# GPS_radiologger_v18_LoRa_only.net
KiCad netlist of a schematic drawn in EAGLE
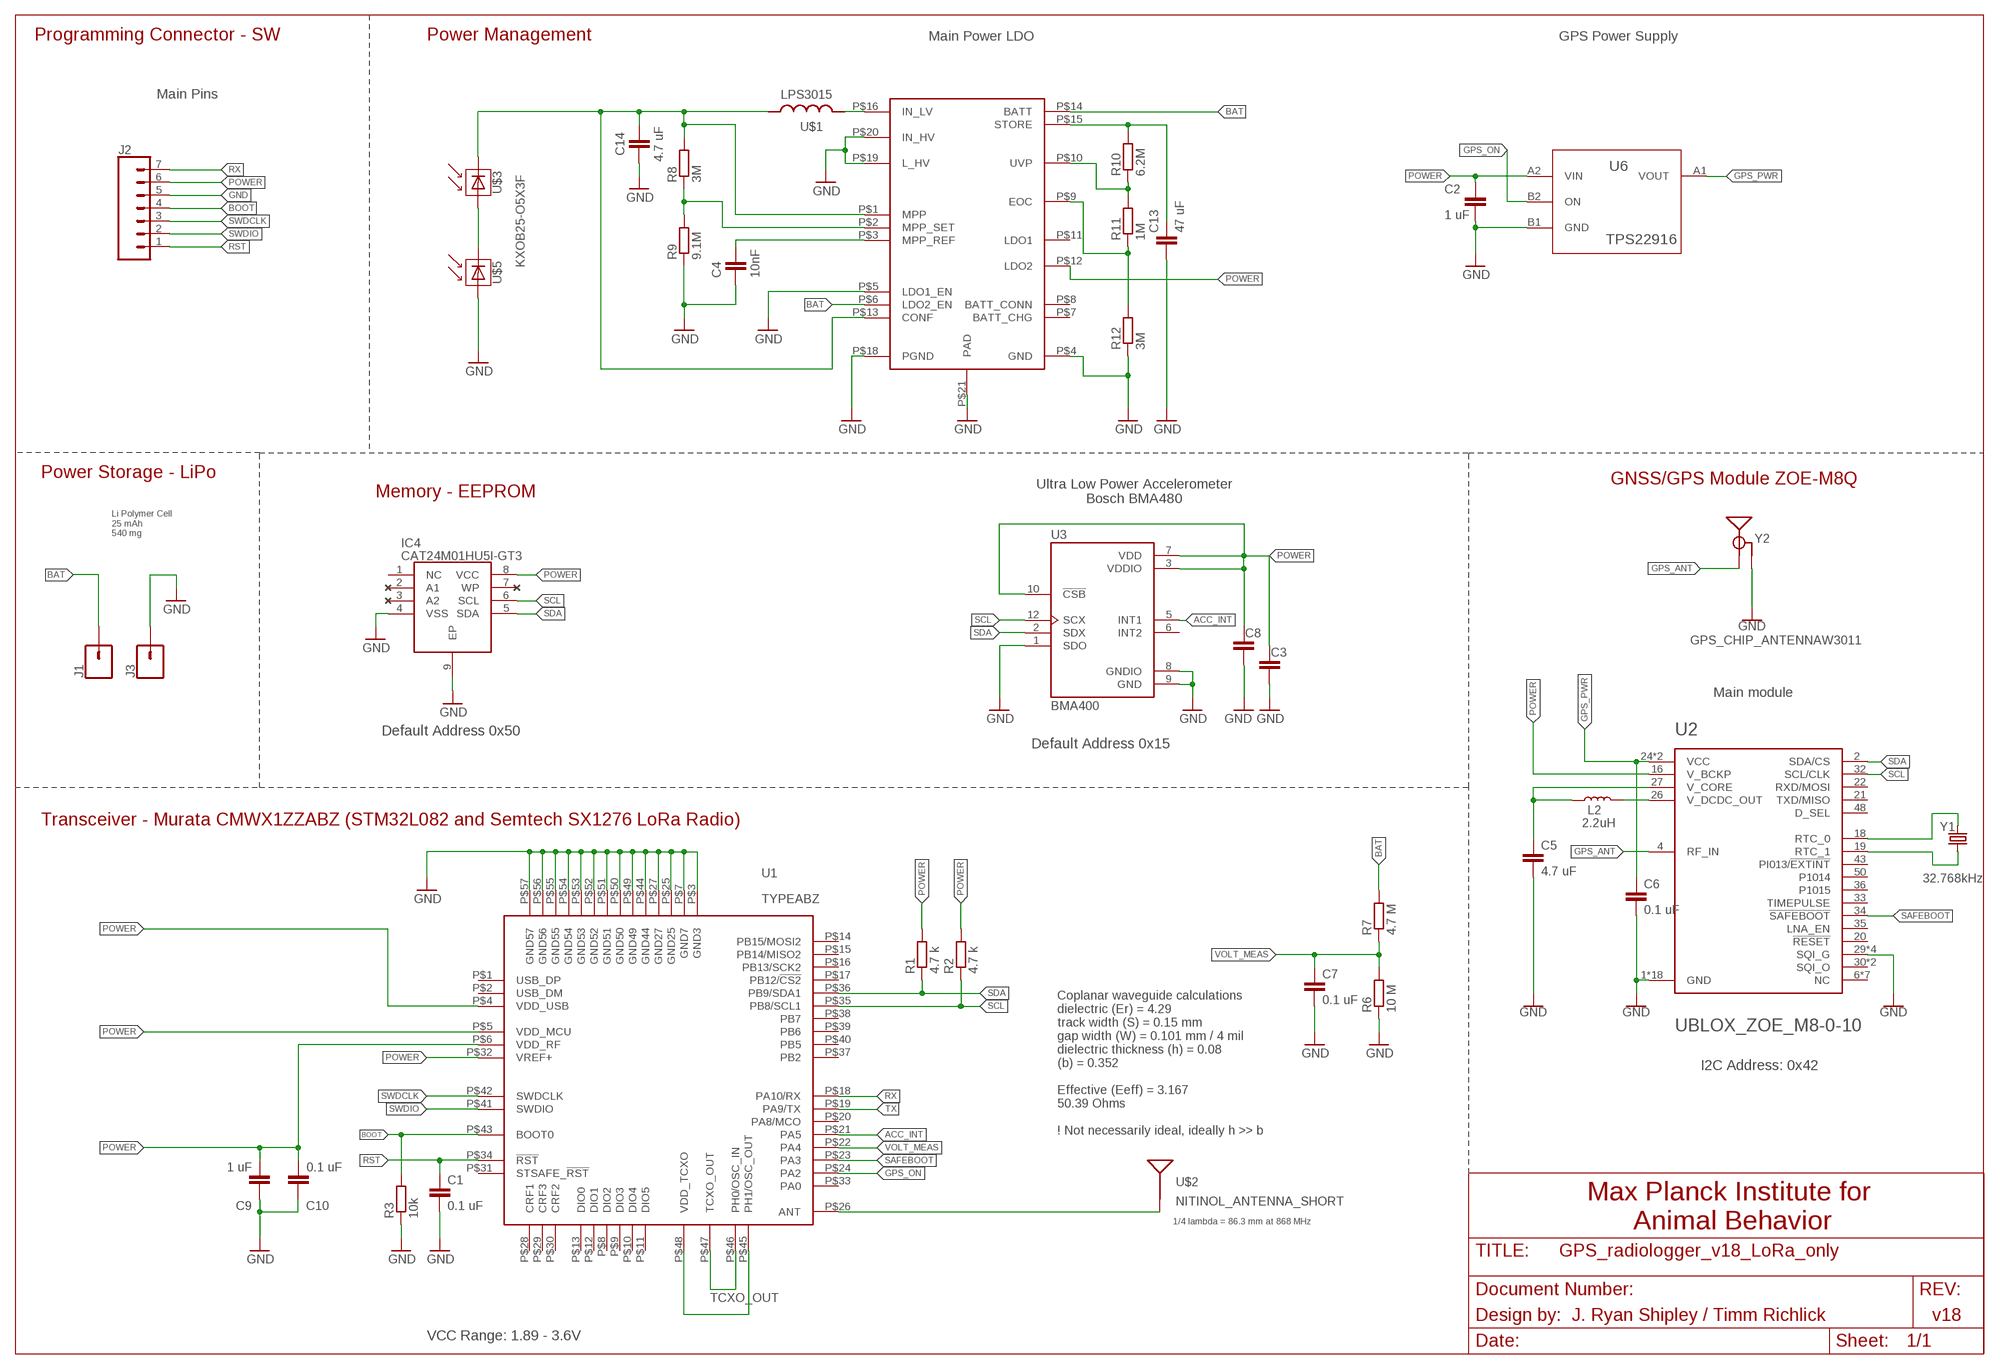
[diagram p0: schematic, sheet 1]

(export (version "E")
  (design (tool "Eeschema 10.0.6"))
  (components
    (comp (ref "C1")
      (value "0.1 uF")
      (footprint "eagle-import:C0201")
      (libsource (lib "eagle-import") (part "C-EUC0201"))
    )
    (comp (ref "C2")
      (value "1 uF")
      (footprint "eagle-import:C0201")
      (libsource (lib "eagle-import") (part "C-EUC0201"))
    )
    (comp (ref "C3")
      (value "C-EUC0201")
      (footprint "eagle-import:C0201")
      (libsource (lib "eagle-import") (part "C-EUC0201"))
    )
    (comp (ref "C4")
      (value "10nF")
      (footprint "eagle-import:C0201")
      (libsource (lib "eagle-import") (part "C-EUC0201"))
    )
    (comp (ref "C5")
      (value "4.7 uF")
      (footprint "eagle-import:C0201")
      (libsource (lib "eagle-import") (part "C-EUC0201"))
    )
    (comp (ref "C6")
      (value "0.1 uF")
      (footprint "eagle-import:C0201")
      (libsource (lib "eagle-import") (part "C-EUC0201"))
    )
    (comp (ref "C7")
      (value "0.1 uF")
      (footprint "eagle-import:C0201")
      (libsource (lib "eagle-import") (part "C-EUC0201"))
    )
    (comp (ref "C8")
      (value "C-EUC0201")
      (footprint "eagle-import:C0201")
      (libsource (lib "eagle-import") (part "C-EUC0201"))
    )
    (comp (ref "C9")
      (value "1 uF")
      (footprint "eagle-import:C0201")
      (libsource (lib "eagle-import") (part "C-EUC0201"))
    )
    (comp (ref "C10")
      (value "0.1 uF")
      (footprint "eagle-import:C0201")
      (libsource (lib "eagle-import") (part "C-EUC0201"))
    )
    (comp (ref "C13")
      (value "47 uF")
      (footprint "eagle-import:C0805K")
      (libsource (lib "eagle-import") (part "C-EUC0805K"))
    )
    (comp (ref "C14")
      (value "4.7 uF")
      (footprint "eagle-import:C0201")
      (libsource (lib "eagle-import") (part "C-EUC0201"))
    )
    (comp (ref "IC4")
      (value "CAT24M01HU5I-GT3")
      (footprint "eagle-import:SON50P300X200X55-9N")
      (fields
        (field (name "MOUSER_PART_NUMBER") "863-CAT24M01HU5I-GT3")
        (field (name "RS_PART_NUMBER") "7814831P")
      )
      (libsource (lib "eagle-import") (part "CAT24M01HU5I-GT3"))
    )
    (comp (ref "J1")
      (value "CONN_01PTH_NO_SILK_YES_STOP")
      (footprint "eagle-import:1X01_NO_SILK")
      (libsource (lib "eagle-import") (part "CONN_01PTH_NO_SILK_YES_STOP"))
    )
    (comp (ref "J2")
      (value "CONN_07NO_SILK")
      (footprint "eagle-import:1X07_NO_SILK")
      (libsource (lib "eagle-import") (part "CONN_07NO_SILK"))
    )
    (comp (ref "J3")
      (value "CONN_01PTH_NO_SILK_YES_STOP")
      (footprint "eagle-import:1X01_NO_SILK")
      (libsource (lib "eagle-import") (part "CONN_01PTH_NO_SILK_YES_STOP"))
    )
    (comp (ref "L2")
      (value "2.2uH")
      (footprint "eagle-import:0806")
      (libsource (lib "eagle-import") (part "2.2μH_SHIELDED_INDUCTOR"))
    )
    (comp (ref "R1")
      (value "4.7 k")
      (footprint "eagle-import:R0201")
      (libsource (lib "eagle-import") (part "R-EU_R0201"))
    )
    (comp (ref "R2")
      (value "4.7 k")
      (footprint "eagle-import:R0201")
      (libsource (lib "eagle-import") (part "R-EU_R0201"))
    )
    (comp (ref "R3")
      (value "10k")
      (footprint "eagle-import:R0201")
      (libsource (lib "eagle-import") (part "R-EU_R0201"))
    )
    (comp (ref "R6")
      (value "10 M")
      (footprint "eagle-import:R0201")
      (libsource (lib "eagle-import") (part "R-EU_R0201"))
    )
    (comp (ref "R7")
      (value "4.7 M")
      (footprint "eagle-import:R0201")
      (libsource (lib "eagle-import") (part "R-EU_R0201"))
    )
    (comp (ref "R8")
      (value "3M")
      (footprint "eagle-import:R0201")
      (libsource (lib "eagle-import") (part "R-EU_R0201"))
    )
    (comp (ref "R9")
      (value "9.1M")
      (footprint "eagle-import:R0201")
      (libsource (lib "eagle-import") (part "R-EU_R0201"))
    )
    (comp (ref "R10")
      (value "6.2M")
      (footprint "eagle-import:R0201")
      (libsource (lib "eagle-import") (part "R-EU_R0201"))
    )
    (comp (ref "R11")
      (value "1M")
      (footprint "eagle-import:R0201")
      (libsource (lib "eagle-import") (part "R-EU_R0201"))
    )
    (comp (ref "R12")
      (value "3M")
      (footprint "eagle-import:R0201")
      (libsource (lib "eagle-import") (part "R-EU_R0201"))
    )
    (comp (ref "U$1")
      (value "LPS3015")
      (footprint "eagle-import:LPS_3015")
      (libsource (lib "eagle-import") (part "LPS3015"))
    )
    (comp (ref "U$2")
      (value "NITINOL_ANTENNA_SHORT")
      (footprint "eagle-import:ICARUS_NITINOL_ANTENNA_SHORT")
      (libsource (lib "eagle-import") (part "NITINOL_ANTENNA_SHORT"))
    )
    (comp (ref "U$3")
      (value "KXOB25-O5X3F")
      (footprint "eagle-import:KXOB25-05X3F")
      (libsource (lib "eagle-import") (part "KXOB25-O5X3F"))
    )
    (comp (ref "U$5")
      (value "KXOB25-O5X3F")
      (footprint "eagle-import:KXOB25-05X3F")
      (libsource (lib "eagle-import") (part "KXOB25-O5X3F"))
    )
    (comp (ref "U1")
      (value "TYPEABZ")
      (footprint "eagle-import:TYPEABZ")
      (libsource (lib "eagle-import") (part "TYPEABZ"))
    )
    (comp (ref "U2")
      (value "UBLOX_ZOE_M8-0-10")
      (footprint "eagle-import:UBLOX_ZOE_M8-0-10")
      (libsource (lib "eagle-import") (part "UBLOX_ZOE_M8-0-10"))
    )
    (comp (ref "U3")
      (value "BMA400")
      (footprint "eagle-import:XDCR_BMA400")
      (fields (field (name "MF") "Bosch Sensortec"))
      (libsource (lib "eagle-import") (part "BMA400"))
    )
    (comp (ref "U4")
      (value "SPV1050")
      (footprint "eagle-import:SPV1050")
      (libsource (lib "eagle-import") (part "SPV1050"))
    )
    (comp (ref "U6")
      (value "TPS22916")
      (footprint "eagle-import:TPS22916")
      (fields (field (name "MF") "Texas Instruments") (field (name "MP") "LP5900TL-3.0"))
      (libsource (lib "eagle-import") (part "TPS22916"))
    )
    (comp (ref "Y1")
      (value "32.768kHz")
      (footprint "eagle-import:CRYSTAL-SMD-3.2X1.5MM")
      (libsource (lib "eagle-import") (part "CRYSTAL-32.768KHZSMD-3.2X1.5"))
    )
    (comp (ref "Y2")
      (value "GPS_CHIP_ANTENNAW3011")
      (footprint "eagle-import:W3011")
      (libsource (lib "eagle-import") (part "GPS_CHIP_ANTENNAW3011"))
    )
  )
  (nets
    (net (code "1") (name "/TCXO_OUT") (class "Default")
      (node (ref "U1") (pin "P$46") (pinfunction "PH0/OSC_IN_P$46") (pintype "bidirectional"))
      (node (ref "U1") (pin "P$47") (pinfunction "TCXO_OUT_P$47") (pintype "bidirectional"))
    )
    (net (code "2") (name "ACC_INT") (class "Default")
      (node (ref "U1") (pin "P$21") (pinfunction "PA5_P$21") (pintype "bidirectional"))
      (node (ref "U3") (pin "5") (pinfunction "INT1_5") (pintype "bidirectional"))
    )
    (net (code "3") (name "BAT") (class "Default")
      (node (ref "J1") (pin "1") (pinfunction "1_1") (pintype "passive"))
      (node (ref "R7") (pin "2") (pinfunction "2_2") (pintype "passive"))
      (node (ref "U4") (pin "P$14") (pinfunction "BATT_P$14") (pintype "bidirectional"))
      (node (ref "U4") (pin "P$6") (pinfunction "LDO2_EN_P$6") (pintype "input"))
    )
    (net (code "4") (name "BOOT") (class "Default")
      (node (ref "J2") (pin "4") (pinfunction "4_4") (pintype "passive"))
      (node (ref "R3") (pin "2") (pinfunction "2_2") (pintype "passive"))
      (node (ref "U1") (pin "P$43") (pinfunction "BOOT0_P$43") (pintype "bidirectional"))
    )
    (net (code "5") (name "GND") (class "Default")
      (node (ref "C1") (pin "2") (pinfunction "2_2") (pintype "passive"))
      (node (ref "C10") (pin "1") (pinfunction "1_1") (pintype "passive"))
      (node (ref "C13") (pin "2") (pinfunction "2_2") (pintype "passive"))
      (node (ref "C14") (pin "2") (pinfunction "2_2") (pintype "passive"))
      (node (ref "C2") (pin "2") (pinfunction "2_2") (pintype "passive"))
      (node (ref "C3") (pin "2") (pinfunction "2_2") (pintype "passive"))
      (node (ref "C4") (pin "2") (pinfunction "2_2") (pintype "passive"))
      (node (ref "C5") (pin "2") (pinfunction "2_2") (pintype "passive"))
      (node (ref "C6") (pin "2") (pinfunction "2_2") (pintype "passive"))
      (node (ref "C7") (pin "2") (pinfunction "2_2") (pintype "passive"))
      (node (ref "C8") (pin "2") (pinfunction "2_2") (pintype "passive"))
      (node (ref "C9") (pin "1") (pinfunction "1_1") (pintype "passive"))
      (node (ref "IC4") (pin "4") (pinfunction "VSS_4") (pintype "power_in"))
      (node (ref "IC4") (pin "9") (pinfunction "EP_9") (pintype "bidirectional"))
      (node (ref "J2") (pin "5") (pinfunction "5_5") (pintype "passive"))
      (node (ref "J3") (pin "1") (pinfunction "1_1") (pintype "passive"))
      (node (ref "R12") (pin "1") (pinfunction "1_1") (pintype "passive"))
      (node (ref "R3") (pin "1") (pinfunction "1_1") (pintype "passive"))
      (node (ref "R6") (pin "1") (pinfunction "1_1") (pintype "passive"))
      (node (ref "R9") (pin "1") (pinfunction "1_1") (pintype "passive"))
      (node (ref "U$5") (pin "P$2") (pinfunction "MINUS_P$2") (pintype "passive"))
      (node (ref "U1") (pin "P$25") (pinfunction "GND25_P$25") (pintype "power_in"))
      (node (ref "U1") (pin "P$27") (pinfunction "GND27_P$27") (pintype "power_in"))
      (node (ref "U1") (pin "P$3") (pinfunction "GND3_P$3") (pintype "power_in"))
      (node (ref "U1") (pin "P$44") (pinfunction "GND44_P$44") (pintype "power_in"))
      (node (ref "U1") (pin "P$49") (pinfunction "GND49_P$49") (pintype "power_in"))
      (node (ref "U1") (pin "P$50") (pinfunction "GND50_P$50") (pintype "power_in"))
      (node (ref "U1") (pin "P$51") (pinfunction "GND51_P$51") (pintype "power_in"))
      (node (ref "U1") (pin "P$52") (pinfunction "GND52_P$52") (pintype "power_in"))
      (node (ref "U1") (pin "P$53") (pinfunction "GND53_P$53") (pintype "power_in"))
      (node (ref "U1") (pin "P$54") (pinfunction "GND54_P$54") (pintype "power_in"))
      (node (ref "U1") (pin "P$55") (pinfunction "GND55_P$55") (pintype "power_in"))
      (node (ref "U1") (pin "P$56") (pinfunction "GND56_P$56") (pintype "power_in"))
      (node (ref "U1") (pin "P$57") (pinfunction "GND57_P$57") (pintype "power_in"))
      (node (ref "U1") (pin "P$7") (pinfunction "GND7_P$7") (pintype "power_in"))
      (node (ref "U2") (pin "1") (pinfunction "GND_1") (pintype "power_in"))
      (node (ref "U2") (pin "10") (pinfunction "GND_10") (pintype "power_in"))
      (node (ref "U2") (pin "11") (pinfunction "GND_11") (pintype "power_in"))
      (node (ref "U2") (pin "12") (pinfunction "GND_12") (pintype "power_in"))
      (node (ref "U2") (pin "17") (pinfunction "GND_17") (pintype "power_in"))
      (node (ref "U2") (pin "23") (pinfunction "GND_23") (pintype "power_in"))
      (node (ref "U2") (pin "29") (pinfunction "SQI_G_29") (pintype "bidirectional"))
      (node (ref "U2") (pin "3") (pinfunction "GND_3") (pintype "power_in"))
      (node (ref "U2") (pin "31") (pinfunction "SQI_G_31") (pintype "bidirectional"))
      (node (ref "U2") (pin "37") (pinfunction "GND_37") (pintype "power_in"))
      (node (ref "U2") (pin "38") (pinfunction "GND_38") (pintype "power_in"))
      (node (ref "U2") (pin "39") (pinfunction "GND_39") (pintype "power_in"))
      (node (ref "U2") (pin "40") (pinfunction "GND_40") (pintype "power_in"))
      (node (ref "U2") (pin "41") (pinfunction "GND_41") (pintype "power_in"))
      (node (ref "U2") (pin "44") (pinfunction "GND_44") (pintype "power_in"))
      (node (ref "U2") (pin "46") (pinfunction "SQI_G_46") (pintype "bidirectional"))
      (node (ref "U2") (pin "47") (pinfunction "SQI_G_47") (pintype "bidirectional"))
      (node (ref "U2") (pin "49") (pinfunction "GND_49") (pintype "power_in"))
      (node (ref "U2") (pin "5") (pinfunction "GND_5") (pintype "power_in"))
      (node (ref "U2") (pin "7") (pinfunction "GND_7") (pintype "power_in"))
      (node (ref "U2") (pin "8") (pinfunction "GND_8") (pintype "power_in"))
      (node (ref "U2") (pin "9") (pinfunction "GND_9") (pintype "power_in"))
      (node (ref "U3") (pin "1") (pinfunction "SDO_1") (pintype "bidirectional"))
      (node (ref "U3") (pin "8") (pinfunction "GNDIO_8") (pintype "power_in"))
      (node (ref "U3") (pin "9") (pinfunction "GND_9") (pintype "power_in"))
      (node (ref "U4") (pin "P$18") (pinfunction "PGND_P$18") (pintype "power_in"))
      (node (ref "U4") (pin "P$19") (pinfunction "L_HV_P$19") (pintype "power_in"))
      (node (ref "U4") (pin "P$20") (pinfunction "IN_HV_P$20") (pintype "power_in"))
      (node (ref "U4") (pin "P$21") (pinfunction "PAD_P$21") (pintype "power_in"))
      (node (ref "U4") (pin "P$4") (pinfunction "GND_P$4") (pintype "power_in"))
      (node (ref "U4") (pin "P$5") (pinfunction "LDO1_EN_P$5") (pintype "input"))
      (node (ref "U6") (pin "B1") (pinfunction "GND_B1") (pintype "passive"))
      (node (ref "Y2") (pin "2") (pinfunction "GND_2") (pintype "bidirectional"))
      (node (ref "Y2") (pin "3") (pinfunction "GND_3") (pintype "bidirectional"))
    )
    (net (code "6") (name "GPS_ANT") (class "Default")
      (node (ref "U2") (pin "4") (pinfunction "RF_IN_4") (pintype "bidirectional"))
      (node (ref "Y2") (pin "1") (pinfunction "SIGNAL_1") (pintype "bidirectional"))
    )
    (net (code "7") (name "GPS_ON") (class "Default")
      (node (ref "U1") (pin "P$24") (pinfunction "PA2_P$24") (pintype "bidirectional"))
      (node (ref "U6") (pin "B2") (pinfunction "ON_B2") (pintype "input"))
    )
    (net (code "8") (name "GPS_PWR") (class "Default")
      (node (ref "C6") (pin "1") (pinfunction "1_1") (pintype "passive"))
      (node (ref "U2") (pin "24") (pinfunction "VCC_24") (pintype "power_in"))
      (node (ref "U2") (pin "25") (pinfunction "VCC_25") (pintype "power_in"))
      (node (ref "U6") (pin "A1") (pinfunction "VOUT_A1") (pintype "output"))
    )
    (net (code "9") (name "Net-(U$1-1)") (class "Default")
      (node (ref "C14") (pin "1") (pinfunction "1_1") (pintype "passive"))
      (node (ref "R8") (pin "2") (pinfunction "2_2") (pintype "passive"))
      (node (ref "U$1") (pin "P$1") (pinfunction "1_P$1") (pintype "passive"))
      (node (ref "U$3") (pin "P$1") (pinfunction "PLUS_P$1") (pintype "passive"))
      (node (ref "U4") (pin "P$1") (pinfunction "MPP_P$1") (pintype "input"))
      (node (ref "U4") (pin "P$13") (pinfunction "CONF_P$13") (pintype "input"))
    )
    (net (code "10") (name "Net-(U$1-2)") (class "Default")
      (node (ref "U$1") (pin "P$2") (pinfunction "2_P$2") (pintype "passive"))
      (node (ref "U4") (pin "P$16") (pinfunction "IN_LV_P$16") (pintype "power_in"))
    )
    (net (code "11") (name "Net-(U$3-MINUS)") (class "Default")
      (node (ref "U$3") (pin "P$2") (pinfunction "MINUS_P$2") (pintype "passive"))
      (node (ref "U$5") (pin "P$1") (pinfunction "PLUS_P$1") (pintype "passive"))
    )
    (net (code "12") (name "Net-(U1-ANT)") (class "Default")
      (node (ref "U$2") (pin "1") (pinfunction "SIGNAL_1") (pintype "bidirectional"))
      (node (ref "U$2") (pin "2") (pinfunction "SIGNAL_2") (pintype "bidirectional"))
      (node (ref "U$2") (pin "3") (pinfunction "SIGNAL_3") (pintype "bidirectional"))
      (node (ref "U1") (pin "P$26") (pinfunction "ANT_P$26") (pintype "bidirectional"))
    )
    (net (code "13") (name "Net-(U1-PH1{slash}OSC_OUT)") (class "Default")
      (node (ref "U1") (pin "P$45") (pinfunction "PH1/OSC_OUT_P$45") (pintype "bidirectional"))
      (node (ref "U1") (pin "P$48") (pinfunction "VDD_TCXO_P$48") (pintype "power_in"))
    )
    (net (code "14") (name "Net-(U2-RTC_0)") (class "Default")
      (node (ref "U2") (pin "18") (pinfunction "RTC_0_18") (pintype "bidirectional"))
      (node (ref "Y1") (pin "P$2") (pinfunction "2_P$2") (pintype "passive"))
    )
    (net (code "15") (name "Net-(U2-RTC_1)") (class "Default")
      (node (ref "U2") (pin "19") (pinfunction "RTC_1_19") (pintype "bidirectional"))
      (node (ref "Y1") (pin "P$1") (pinfunction "1_P$1") (pintype "passive"))
    )
    (net (code "16") (name "Net-(U2-V_CORE)") (class "Default")
      (node (ref "C5") (pin "1") (pinfunction "1_1") (pintype "passive"))
      (node (ref "L2") (pin "1") (pinfunction "1_1") (pintype "passive"))
      (node (ref "U2") (pin "27") (pinfunction "V_CORE_27") (pintype "power_in"))
    )
    (net (code "17") (name "Net-(U2-V_DCDC_OUT)") (class "Default")
      (node (ref "L2") (pin "2") (pinfunction "2_2") (pintype "passive"))
      (node (ref "U2") (pin "26") (pinfunction "V_DCDC_OUT_26") (pintype "power_in"))
    )
    (net (code "18") (name "Net-(U4-EOC)") (class "Default")
      (node (ref "R11") (pin "1") (pinfunction "1_1") (pintype "passive"))
      (node (ref "R12") (pin "2") (pinfunction "2_2") (pintype "passive"))
      (node (ref "U4") (pin "P$9") (pinfunction "EOC_P$9") (pintype "input"))
    )
    (net (code "19") (name "Net-(U4-MPP_REF)") (class "Default")
      (node (ref "C4") (pin "1") (pinfunction "1_1") (pintype "passive"))
      (node (ref "U4") (pin "P$3") (pinfunction "MPP_REF_P$3") (pintype "input"))
    )
    (net (code "20") (name "Net-(U4-MPP_SET)") (class "Default")
      (node (ref "R8") (pin "1") (pinfunction "1_1") (pintype "passive"))
      (node (ref "R9") (pin "2") (pinfunction "2_2") (pintype "passive"))
      (node (ref "U4") (pin "P$2") (pinfunction "MPP_SET_P$2") (pintype "input"))
    )
    (net (code "21") (name "Net-(U4-STORE)") (class "Default")
      (node (ref "C13") (pin "1") (pinfunction "1_1") (pintype "passive"))
      (node (ref "R10") (pin "2") (pinfunction "2_2") (pintype "passive"))
      (node (ref "U4") (pin "P$15") (pinfunction "STORE_P$15") (pintype "bidirectional"))
    )
    (net (code "22") (name "Net-(U4-UVP)") (class "Default")
      (node (ref "R10") (pin "1") (pinfunction "1_1") (pintype "passive"))
      (node (ref "R11") (pin "2") (pinfunction "2_2") (pintype "passive"))
      (node (ref "U4") (pin "P$10") (pinfunction "UVP_P$10") (pintype "input"))
    )
    (net (code "23") (name "POWER") (class "Default")
      (node (ref "C10") (pin "2") (pinfunction "2_2") (pintype "passive"))
      (node (ref "C2") (pin "1") (pinfunction "1_1") (pintype "passive"))
      (node (ref "C3") (pin "1") (pinfunction "1_1") (pintype "passive"))
      (node (ref "C8") (pin "1") (pinfunction "1_1") (pintype "passive"))
      (node (ref "C9") (pin "2") (pinfunction "2_2") (pintype "passive"))
      (node (ref "IC4") (pin "8") (pinfunction "VCC_8") (pintype "power_in"))
      (node (ref "J2") (pin "6") (pinfunction "6_6") (pintype "passive"))
      (node (ref "R1") (pin "2") (pinfunction "2_2") (pintype "passive"))
      (node (ref "R2") (pin "2") (pinfunction "2_2") (pintype "passive"))
      (node (ref "U1") (pin "P$32") (pinfunction "VREF+_P$32") (pintype "power_in"))
      (node (ref "U1") (pin "P$4") (pinfunction "VDD_USB_P$4") (pintype "power_in"))
      (node (ref "U1") (pin "P$5") (pinfunction "VDD_MCU_P$5") (pintype "power_in"))
      (node (ref "U1") (pin "P$6") (pinfunction "VDD_RF_P$6") (pintype "power_in"))
      (node (ref "U2") (pin "16") (pinfunction "V_BCKP_16") (pintype "power_in"))
      (node (ref "U3") (pin "10") (pinfunction "~{CSB}_10") (pintype "input"))
      (node (ref "U3") (pin "3") (pinfunction "VDDIO_3") (pintype "power_in"))
      (node (ref "U3") (pin "7") (pinfunction "VDD_7") (pintype "power_in"))
      (node (ref "U4") (pin "P$12") (pinfunction "LDO2_P$12") (pintype "output"))
      (node (ref "U6") (pin "A2") (pinfunction "VIN_A2") (pintype "power_in"))
    )
    (net (code "24") (name "RST") (class "Default")
      (node (ref "C1") (pin "1") (pinfunction "1_1") (pintype "passive"))
      (node (ref "J2") (pin "1") (pinfunction "1_1") (pintype "passive"))
      (node (ref "U1") (pin "P$34") (pinfunction "~{RST}_P$34") (pintype "bidirectional"))
    )
    (net (code "25") (name "RX") (class "Default")
      (node (ref "J2") (pin "7") (pinfunction "7_7") (pintype "passive"))
      (node (ref "U1") (pin "P$18") (pinfunction "PA10/RX_P$18") (pintype "bidirectional"))
    )
    (net (code "26") (name "SAFEBOOT") (class "Default")
      (node (ref "U1") (pin "P$23") (pinfunction "PA3_P$23") (pintype "bidirectional"))
      (node (ref "U2") (pin "34") (pinfunction "~{SAFEBOOT}_34") (pintype "bidirectional"))
    )
    (net (code "27") (name "SCL") (class "Default")
      (node (ref "IC4") (pin "6") (pinfunction "SCL_6") (pintype "bidirectional"))
      (node (ref "R2") (pin "1") (pinfunction "1_1") (pintype "passive"))
      (node (ref "U1") (pin "P$35") (pinfunction "PB8/SCL1_P$35") (pintype "bidirectional"))
      (node (ref "U2") (pin "32") (pinfunction "SCL/CLK_32") (pintype "bidirectional"))
      (node (ref "U3") (pin "12") (pinfunction "SCX_12") (pintype "input"))
    )
    (net (code "28") (name "SDA") (class "Default")
      (node (ref "IC4") (pin "5") (pinfunction "SDA_5") (pintype "bidirectional"))
      (node (ref "R1") (pin "1") (pinfunction "1_1") (pintype "passive"))
      (node (ref "U1") (pin "P$36") (pinfunction "PB9/SDA1_P$36") (pintype "bidirectional"))
      (node (ref "U2") (pin "2") (pinfunction "SDA/CS_2") (pintype "bidirectional"))
      (node (ref "U3") (pin "2") (pinfunction "SDX_2") (pintype "bidirectional"))
    )
    (net (code "29") (name "SWDCLK") (class "Default")
      (node (ref "J2") (pin "3") (pinfunction "3_3") (pintype "passive"))
      (node (ref "U1") (pin "P$42") (pinfunction "SWDCLK_P$42") (pintype "bidirectional"))
    )
    (net (code "30") (name "SWDIO") (class "Default")
      (node (ref "J2") (pin "2") (pinfunction "2_2") (pintype "passive"))
      (node (ref "U1") (pin "P$41") (pinfunction "SWDIO_P$41") (pintype "bidirectional"))
    )
    (net (code "31") (name "TX") (class "Default")
      (node (ref "U1") (pin "P$19") (pinfunction "PA9/TX_P$19") (pintype "bidirectional"))
    )
    (net (code "32") (name "VOLT_MEAS") (class "Default")
      (node (ref "C7") (pin "1") (pinfunction "1_1") (pintype "passive"))
      (node (ref "R6") (pin "2") (pinfunction "2_2") (pintype "passive"))
      (node (ref "R7") (pin "1") (pinfunction "1_1") (pintype "passive"))
      (node (ref "U1") (pin "P$22") (pinfunction "PA4_P$22") (pintype "bidirectional"))
    )
    (net (code "33") (name "unconnected-(IC4-A1-Pad2)") (class "Default")
      (node (ref "IC4") (pin "2") (pinfunction "A1_2") (pintype "bidirectional"))
    )
    (net (code "34") (name "unconnected-(IC4-A2-Pad3)") (class "Default")
      (node (ref "IC4") (pin "3") (pinfunction "A2_3") (pintype "bidirectional"))
    )
    (net (code "35") (name "unconnected-(IC4-NC-Pad1)") (class "Default")
      (node (ref "IC4") (pin "1") (pinfunction "NC_1") (pintype "no_connect"))
    )
    (net (code "36") (name "unconnected-(IC4-WP-Pad7)") (class "Default")
      (node (ref "IC4") (pin "7") (pinfunction "WP_7") (pintype "bidirectional"))
    )
    (net (code "37") (name "unconnected-(U1-CRF1-PadP$28)") (class "Default")
      (node (ref "U1") (pin "P$28") (pinfunction "CRF1_P$28") (pintype "no_connect"))
    )
    (net (code "38") (name "unconnected-(U1-CRF2-PadP$30)") (class "Default")
      (node (ref "U1") (pin "P$30") (pinfunction "CRF2_P$30") (pintype "no_connect"))
    )
    (net (code "39") (name "unconnected-(U1-CRF3-PadP$29)") (class "Default")
      (node (ref "U1") (pin "P$29") (pinfunction "CRF3_P$29") (pintype "no_connect"))
    )
    (net (code "40") (name "unconnected-(U1-DIO0-PadP$13)") (class "Default")
      (node (ref "U1") (pin "P$13") (pinfunction "DIO0_P$13") (pintype "no_connect"))
    )
    (net (code "41") (name "unconnected-(U1-DIO1-PadP$12)") (class "Default")
      (node (ref "U1") (pin "P$12") (pinfunction "DIO1_P$12") (pintype "no_connect"))
    )
    (net (code "42") (name "unconnected-(U1-DIO2-PadP$8)") (class "Default")
      (node (ref "U1") (pin "P$8") (pinfunction "DIO2_P$8") (pintype "no_connect"))
    )
    (net (code "43") (name "unconnected-(U1-DIO3-PadP$9)") (class "Default")
      (node (ref "U1") (pin "P$9") (pinfunction "DIO3_P$9") (pintype "no_connect"))
    )
    (net (code "44") (name "unconnected-(U1-DIO4-PadP$10)") (class "Default")
      (node (ref "U1") (pin "P$10") (pinfunction "DIO4_P$10") (pintype "bidirectional"))
    )
    (net (code "45") (name "unconnected-(U1-DIO5-PadP$11)") (class "Default")
      (node (ref "U1") (pin "P$11") (pinfunction "DIO5_P$11") (pintype "bidirectional"))
    )
    (net (code "46") (name "unconnected-(U1-PA0-PadP$33)") (class "Default")
      (node (ref "U1") (pin "P$33") (pinfunction "PA0_P$33") (pintype "bidirectional"))
    )
    (net (code "47") (name "unconnected-(U1-PA8{slash}MCO-PadP$20)") (class "Default")
      (node (ref "U1") (pin "P$20") (pinfunction "PA8/MCO_P$20") (pintype "bidirectional"))
    )
    (net (code "48") (name "unconnected-(U1-PB2-PadP$37)") (class "Default")
      (node (ref "U1") (pin "P$37") (pinfunction "PB2_P$37") (pintype "bidirectional"))
    )
    (net (code "49") (name "unconnected-(U1-PB5-PadP$40)") (class "Default")
      (node (ref "U1") (pin "P$40") (pinfunction "PB5_P$40") (pintype "bidirectional"))
    )
    (net (code "50") (name "unconnected-(U1-PB6-PadP$39)") (class "Default")
      (node (ref "U1") (pin "P$39") (pinfunction "PB6_P$39") (pintype "bidirectional"))
    )
    (net (code "51") (name "unconnected-(U1-PB7-PadP$38)") (class "Default")
      (node (ref "U1") (pin "P$38") (pinfunction "PB7_P$38") (pintype "bidirectional"))
    )
    (net (code "52") (name "unconnected-(U1-PB12{slash}~{CS2}-PadP$17)") (class "Default")
      (node (ref "U1") (pin "P$17") (pinfunction "PB12/~{CS2}_P$17") (pintype "bidirectional"))
    )
    (net (code "53") (name "unconnected-(U1-PB13{slash}SCK2-PadP$16)") (class "Default")
      (node (ref "U1") (pin "P$16") (pinfunction "PB13/SCK2_P$16") (pintype "bidirectional"))
    )
    (net (code "54") (name "unconnected-(U1-PB14{slash}MISO2-PadP$15)") (class "Default")
      (node (ref "U1") (pin "P$15") (pinfunction "PB14/MISO2_P$15") (pintype "bidirectional"))
    )
    (net (code "55") (name "unconnected-(U1-PB15{slash}MOSI2-PadP$14)") (class "Default")
      (node (ref "U1") (pin "P$14") (pinfunction "PB15/MOSI2_P$14") (pintype "bidirectional"))
    )
    (net (code "56") (name "unconnected-(U1-STSAFE_~{RST}-PadP$31)") (class "Default")
      (node (ref "U1") (pin "P$31") (pinfunction "STSAFE_~{RST}_P$31") (pintype "bidirectional"))
    )
    (net (code "57") (name "unconnected-(U1-USB_DM-PadP$2)") (class "Default")
      (node (ref "U1") (pin "P$2") (pinfunction "USB_DM_P$2") (pintype "bidirectional"))
    )
    (net (code "58") (name "unconnected-(U1-USB_DP-PadP$1)") (class "Default")
      (node (ref "U1") (pin "P$1") (pinfunction "USB_DP_P$1") (pintype "bidirectional"))
    )
    (net (code "59") (name "unconnected-(U2-D_SEL-Pad48)") (class "Default")
      (node (ref "U2") (pin "48") (pinfunction "D_SEL_48") (pintype "bidirectional"))
    )
    (net (code "60") (name "unconnected-(U2-LNA_EN-Pad35)") (class "Default")
      (node (ref "U2") (pin "35") (pinfunction "LNA_EN_35") (pintype "bidirectional"))
    )
    (net (code "61") (name "unconnected-(U2-NC-Pad6)") (class "Default")
      (node (ref "U2") (pin "6") (pinfunction "NC_6") (pintype "no_connect"))
    )
    (net (code "62") (name "unconnected-(U2-NC-Pad13)") (class "Default")
      (node (ref "U2") (pin "13") (pinfunction "NC_13") (pintype "no_connect"))
    )
    (net (code "63") (name "unconnected-(U2-NC-Pad14)") (class "Default")
      (node (ref "U2") (pin "14") (pinfunction "NC_14") (pintype "no_connect"))
    )
    (net (code "64") (name "unconnected-(U2-NC-Pad15)") (class "Default")
      (node (ref "U2") (pin "15") (pinfunction "NC_15") (pintype "no_connect"))
    )
    (net (code "65") (name "unconnected-(U2-NC-Pad28)") (class "Default")
      (node (ref "U2") (pin "28") (pinfunction "NC_28") (pintype "no_connect"))
    )
    (net (code "66") (name "unconnected-(U2-NC-Pad42)") (class "Default")
      (node (ref "U2") (pin "42") (pinfunction "NC_42") (pintype "no_connect"))
    )
    (net (code "67") (name "unconnected-(U2-NC-Pad51)") (class "Default")
      (node (ref "U2") (pin "51") (pinfunction "NC_51") (pintype "no_connect"))
    )
    (net (code "68") (name "unconnected-(U2-P1014-Pad50)") (class "Default")
      (node (ref "U2") (pin "50") (pinfunction "P1014_50") (pintype "bidirectional"))
    )
    (net (code "69") (name "unconnected-(U2-P1015-Pad36)") (class "Default")
      (node (ref "U2") (pin "36") (pinfunction "P1015_36") (pintype "bidirectional"))
    )
    (net (code "70") (name "unconnected-(U2-PI013{slash}~{EXTINT}-Pad43)") (class "Default")
      (node (ref "U2") (pin "43") (pinfunction "PI013/~{EXTINT}_43") (pintype "bidirectional"))
    )
    (net (code "71") (name "unconnected-(U2-RXD{slash}MOSI-Pad22)") (class "Default")
      (node (ref "U2") (pin "22") (pinfunction "RXD/MOSI_22") (pintype "bidirectional"))
    )
    (net (code "72") (name "unconnected-(U2-SQI_O-Pad30)") (class "Default")
      (node (ref "U2") (pin "30") (pinfunction "SQI_O_30") (pintype "no_connect"))
    )
    (net (code "73") (name "unconnected-(U2-SQI_O-Pad45)") (class "Default")
      (node (ref "U2") (pin "45") (pinfunction "SQI_O_45") (pintype "no_connect"))
    )
    (net (code "74") (name "unconnected-(U2-TIMEPULSE-Pad33)") (class "Default")
      (node (ref "U2") (pin "33") (pinfunction "TIMEPULSE_33") (pintype "bidirectional"))
    )
    (net (code "75") (name "unconnected-(U2-TXD{slash}MISO-Pad21)") (class "Default")
      (node (ref "U2") (pin "21") (pinfunction "TXD/MISO_21") (pintype "bidirectional"))
    )
    (net (code "76") (name "unconnected-(U2-~{RESET}-Pad20)") (class "Default")
      (node (ref "U2") (pin "20") (pinfunction "~{RESET}_20") (pintype "bidirectional"))
    )
    (net (code "77") (name "unconnected-(U3-INT2-Pad6)") (class "Default")
      (node (ref "U3") (pin "6") (pinfunction "INT2_6") (pintype "bidirectional"))
    )
    (net (code "78") (name "unconnected-(U4-BATT_CHG-PadP$7)") (class "Default")
      (node (ref "U4") (pin "P$7") (pinfunction "BATT_CHG_P$7") (pintype "open_collector"))
    )
    (net (code "79") (name "unconnected-(U4-BATT_CONN-PadP$8)") (class "Default")
      (node (ref "U4") (pin "P$8") (pinfunction "BATT_CONN_P$8") (pintype "open_collector"))
    )
    (net (code "80") (name "unconnected-(U4-LDO1-PadP$11)") (class "Default")
      (node (ref "U4") (pin "P$11") (pinfunction "LDO1_P$11") (pintype "output"))
    )
  )
)
